# power_supply.net
KiCad netlist of a schematic drawn in Altium Designer
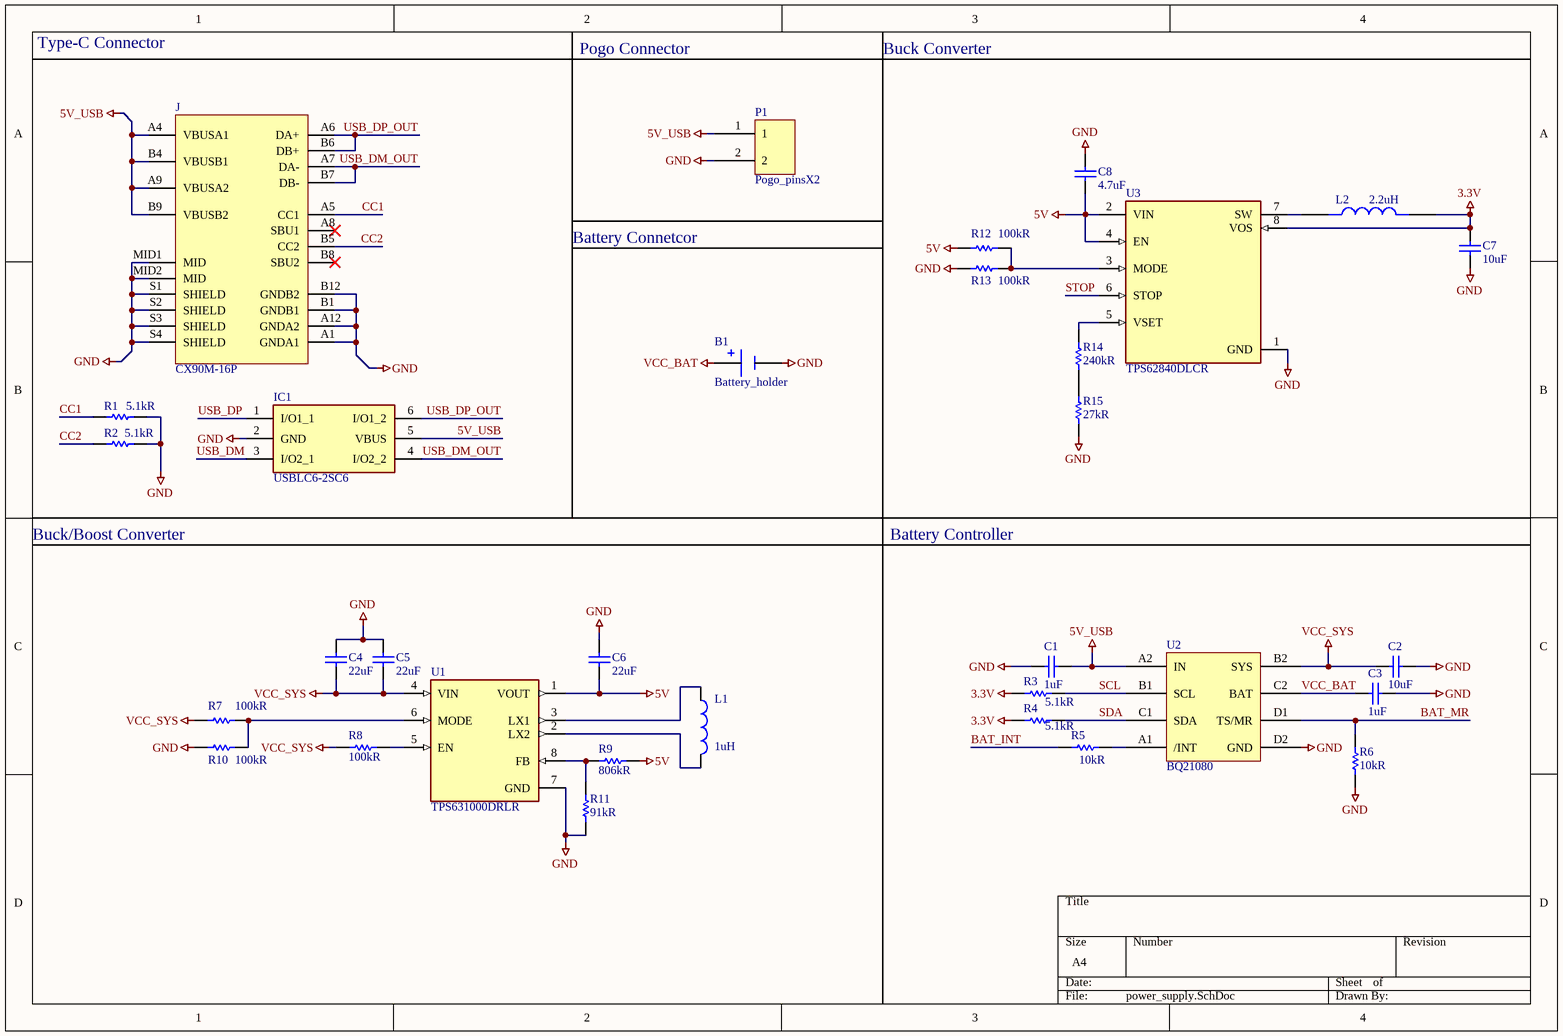
[diagram p0: power_supply.SchDoc]

(export (version "E")
  (design (tool "Eeschema 10.0.6"))
  (components
    (comp (ref "B1")
      (value "Battery_holder")
      (footprint "CHOCO_KEYBOARD:battery connection")
      (description "li-ion 14500 battery holder")
      (libsource (lib "CHOCO_KEYBOARD") (part "Battery_holder"))
    )
    (comp (ref "C1")
      (value "1uF")
      (footprint "CAP_0402")
      (fields (field (name "MF") "Murata") (field (name "MP") "GRM022R60J222KE19L"))
      (libsource (lib "CAP_SMD") (part "Cap_1uF_0402"))
    )
    (comp (ref "C2")
      (value "10uF")
      (footprint "CAP_0402")
      (fields (field (name "MF") "Murata") (field (name "MP") "GRM022R60J222KE19L"))
      (libsource (lib "CAP_SMD") (part "Cap_10uF_0402"))
    )
    (comp (ref "C3")
      (value "1uF")
      (footprint "CAP_0402")
      (fields (field (name "MF") "Murata") (field (name "MP") "GRM022R60J222KE19L"))
      (libsource (lib "CAP_SMD") (part "Cap_1uF_0402"))
    )
    (comp (ref "C4")
      (value "22uF")
      (footprint "CAP_0402")
      (fields (field (name "MF") "Murata") (field (name "MP") "GRM022R60J222KE19L"))
      (libsource (lib "CAP_SMD") (part "Cap_22uF_0402"))
    )
    (comp (ref "C5")
      (value "22uF")
      (footprint "CAP_0402")
      (fields (field (name "MF") "Murata") (field (name "MP") "GRM022R60J222KE19L"))
      (libsource (lib "CAP_SMD") (part "Cap_22uF_0402"))
    )
    (comp (ref "C6")
      (value "22uF")
      (footprint "CAP_0402")
      (fields (field (name "MF") "Murata") (field (name "MP") "GRM022R60J222KE19L"))
      (libsource (lib "CAP_SMD") (part "Cap_22uF_0402"))
    )
    (comp (ref "C7")
      (value "10uF")
      (footprint "CAP_0402")
      (fields (field (name "MF") "Murata") (field (name "MP") "GRM022R60J222KE19L"))
      (libsource (lib "CAP_SMD") (part "Cap_10uF_0402"))
    )
    (comp (ref "C8")
      (value "4.7uF")
      (footprint "CAP_0402")
      (fields (field (name "MF") "Murata") (field (name "MP") "GRM022R60J222KE19L"))
      (libsource (lib "CAP_SMD") (part "Cap_4.7uF_0402"))
    )
    (comp (ref "IC1")
      (value "USBLC6-2SC6")
      (footprint "SOT95P280X145-6N")
      (description "Integrated Circuit")
      (fields (field (name "MOUSER PART NUMBER") "511-USBLC6-2SC6"))
      (libsource (lib "CHOCO_KEYBOARD") (part "USBLC6-2SC6"))
    )
    (comp (ref "J")
      (value "CX90M-16P")
      (footprint "CHOCO_KEYBOARD:HRS_CX90M-16P")
      (fields (field (name "MF") "Hirose Electric Co Ltd"))
      (libsource (lib "CHOCO_KEYBOARD") (part "CX90M-16P"))
    )
    (comp (ref "L1")
      (value "1uH")
      (footprint "INDC1608X100N")
      (description "DFE18SAN1R0MG0L")
      (libsource (lib "DFE18SAN1R0MG0L") (part "DFE18SAN1R0MG0L"))
    )
    (comp (ref "L2")
      (value "2.2uH")
      (footprint "INDC2012X100N")
      (description "2.2 ÂµH Shielded Multilayer Inductor 800 mA 299mOhm Max 0805 (2012 Metric)")
      (fields (field (name "MF") "TDK") (field (name "MP") "MLP2012S2R2MT0S1"))
      (libsource (lib "MLP2012S2R2MT0S1") (part "MLP2012S2R2MT0S1"))
    )
    (comp (ref "P1")
      (value "Pogo_pinsX2")
      (footprint "pogo_2_pins_amgled")
      (libsource (lib "CHOCO_KEYBOARD") (part "Pogo_pinsX2"))
    )
    (comp (ref "R1")
      (value "5.1kR")
      (footprint "RES_0402")
      (libsource (lib "RES_SMD") (part "Res_5.1kR_0402"))
    )
    (comp (ref "R2")
      (value "5.1kR")
      (footprint "RES_0402")
      (libsource (lib "RES_SMD") (part "Res_5.1kR_0402"))
    )
    (comp (ref "R3")
      (value "5.1kR")
      (footprint "RES_0402")
      (libsource (lib "RES_SMD") (part "Res_5.1kR_0402"))
    )
    (comp (ref "R4")
      (value "5.1kR")
      (footprint "RES_0402")
      (libsource (lib "RES_SMD") (part "Res_5.1kR_0402"))
    )
    (comp (ref "R5") (value "10kR") (footprint "RES_0402") (libsource (lib "RES_SMD") (part "Res_10kR_0402")))
    (comp (ref "R6") (value "10kR") (footprint "RES_0402") (libsource (lib "RES_SMD") (part "Res_10kR_0402")))
    (comp (ref "R7")
      (value "100kR")
      (footprint "RES_0402")
      (libsource (lib "RES_SMD") (part "Res_100kR_0402_1"))
    )
    (comp (ref "R8")
      (value "100kR")
      (footprint "RES_0402")
      (libsource (lib "RES_SMD") (part "Res_100kR_0402_1"))
    )
    (comp (ref "R9")
      (value "806kR")
      (footprint "RES_0402")
      (libsource (lib "RES_SMD") (part "Res_806kR_0402_1"))
    )
    (comp (ref "R10")
      (value "100kR")
      (footprint "RES_0402")
      (libsource (lib "RES_SMD") (part "Res_100kR_0402_1"))
    )
    (comp (ref "R11")
      (value "91kR")
      (footprint "RES_0402")
      (libsource (lib "RES_SMD") (part "Res_91kR_0402"))
    )
    (comp (ref "R12")
      (value "100kR")
      (footprint "RES_0402")
      (libsource (lib "RES_SMD") (part "Res_100kR_0402_1"))
    )
    (comp (ref "R13")
      (value "100kR")
      (footprint "RES_0402")
      (libsource (lib "RES_SMD") (part "Res_100kR_0402_1"))
    )
    (comp (ref "R14")
      (value "240kR")
      (footprint "RES_0402")
      (libsource (lib "RES_SMD") (part "Res_240kR_0402"))
    )
    (comp (ref "R15")
      (value "27kR")
      (footprint "RES_0402")
      (libsource (lib "RES_SMD") (part "Res_27kR_0402"))
    )
    (comp (ref "U1")
      (value "TPS631000DRLR")
      (footprint "SOT50P160X60-8N")
      (description "1.5-A output current, high-power-density buck-boost converter")
      (fields (field (name "MF") "Texas Instruments"))
      (libsource (lib "TPS631000DRLR") (part "TPS631000DRLR"))
    )
    (comp (ref "U2")
      (value "BQ21080")
      (footprint "IC_BQ25180YBGR")
      (description "Battery Managment IC")
      (libsource (lib "CHOCO_KEYBOARD") (part "BQ21080"))
    )
    (comp (ref "U3")
      (value "TPS62840DLCR")
      (footprint "SON50P200X150X100-8N")
      (libsource (lib "TPS62840DLCR") (part "TPS62840DLCR"))
    )
  )
  (nets
    (net (code "1") (name "/BAT_INT") (class "Default")
      (node (ref "R5") (pin "2") (pinfunction "2_2") (pintype "passive"))
    )
    (net (code "2") (name "/BAT_MR") (class "Default")
      (node (ref "R6") (pin "1") (pinfunction "1_1") (pintype "passive"))
      (node (ref "U2") (pin "D1") (pinfunction "TS/MR_D1") (pintype "passive"))
    )
    (net (code "3") (name "/CC1") (class "Default")
      (node (ref "J") (pin "A5") (pinfunction "CC1_A5") (pintype "passive"))
      (node (ref "R1") (pin "1") (pinfunction "1_1") (pintype "passive"))
    )
    (net (code "4") (name "/CC2") (class "Default")
      (node (ref "J") (pin "B5") (pinfunction "CC2_B5") (pintype "passive"))
      (node (ref "R2") (pin "1") (pinfunction "1_1") (pintype "passive"))
    )
    (net (code "5") (name "/SCL") (class "Default")
      (node (ref "R3") (pin "1") (pinfunction "1_1") (pintype "passive"))
      (node (ref "U2") (pin "B1") (pinfunction "SCL_B1") (pintype "passive"))
    )
    (net (code "6") (name "/SDA") (class "Default")
      (node (ref "R4") (pin "1") (pinfunction "1_1") (pintype "passive"))
      (node (ref "U2") (pin "C1") (pinfunction "SDA_C1") (pintype "passive"))
    )
    (net (code "7") (name "/STOP") (class "Default")
      (node (ref "U3") (pin "6") (pinfunction "STOP_6") (pintype "input"))
    )
    (net (code "8") (name "/USB_DM") (class "Default")
      (node (ref "IC1") (pin "3") (pinfunction "I/O2_1_3") (pintype "passive"))
    )
    (net (code "9") (name "/USB_DM_OUT") (class "Default")
      (node (ref "IC1") (pin "4") (pinfunction "I/O2_2_4") (pintype "passive"))
      (node (ref "J") (pin "A7") (pinfunction "DA-_A7") (pintype "passive"))
      (node (ref "J") (pin "B7") (pinfunction "DB-_B7") (pintype "passive"))
    )
    (net (code "10") (name "/USB_DP") (class "Default")
      (node (ref "IC1") (pin "1") (pinfunction "I/O1_1_1") (pintype "passive"))
    )
    (net (code "11") (name "/USB_DP_OUT") (class "Default")
      (node (ref "IC1") (pin "6") (pinfunction "I/O1_2_6") (pintype "passive"))
      (node (ref "J") (pin "A6") (pinfunction "DA+_A6") (pintype "passive"))
      (node (ref "J") (pin "B6") (pinfunction "DB+_B6") (pintype "passive"))
    )
    (net (code "12") (name "3.3V") (class "Default")
      (node (ref "C7") (pin "2") (pinfunction "2_2") (pintype "passive"))
      (node (ref "L2") (pin "2") (pinfunction "2_2") (pintype "passive"))
      (node (ref "R3") (pin "2") (pinfunction "2_2") (pintype "passive"))
      (node (ref "R4") (pin "2") (pinfunction "2_2") (pintype "passive"))
      (node (ref "U3") (pin "8") (pinfunction "VOS_8") (pintype "input"))
    )
    (net (code "13") (name "5V") (class "Default")
      (node (ref "C6") (pin "1") (pinfunction "1_1") (pintype "passive"))
      (node (ref "C8") (pin "2") (pinfunction "2_2") (pintype "passive"))
      (node (ref "R12") (pin "1") (pinfunction "1_1") (pintype "passive"))
      (node (ref "R9") (pin "1") (pinfunction "1_1") (pintype "passive"))
      (node (ref "U1") (pin "1") (pinfunction "VOUT_1") (pintype "output"))
      (node (ref "U3") (pin "2") (pinfunction "VIN_2") (pintype "power_in"))
      (node (ref "U3") (pin "4") (pinfunction "EN_4") (pintype "input"))
    )
    (net (code "14") (name "5V_USB") (class "Default")
      (node (ref "C1") (pin "2") (pinfunction "2_2") (pintype "passive"))
      (node (ref "IC1") (pin "5") (pinfunction "VBUS_5") (pintype "passive"))
      (node (ref "J") (pin "A4") (pinfunction "VBUSA1_A4") (pintype "power_in"))
      (node (ref "J") (pin "A9") (pinfunction "VBUSA2_A9") (pintype "power_in"))
      (node (ref "J") (pin "B4") (pinfunction "VBUSB1_B4") (pintype "power_in"))
      (node (ref "J") (pin "B9") (pinfunction "VBUSB2_B9") (pintype "power_in"))
      (node (ref "P1") (pin "1") (pinfunction "1_1") (pintype "passive"))
      (node (ref "U2") (pin "A2") (pinfunction "IN_A2") (pintype "passive"))
    )
    (net (code "15") (name "GND") (class "Default")
      (node (ref "B1") (pin "2") (pinfunction "NEG_2") (pintype "passive"))
      (node (ref "C1") (pin "1") (pinfunction "1_1") (pintype "passive"))
      (node (ref "C2") (pin "1") (pinfunction "1_1") (pintype "passive"))
      (node (ref "C3") (pin "1") (pinfunction "1_1") (pintype "passive"))
      (node (ref "C4") (pin "2") (pinfunction "2_2") (pintype "passive"))
      (node (ref "C5") (pin "2") (pinfunction "2_2") (pintype "passive"))
      (node (ref "C6") (pin "2") (pinfunction "2_2") (pintype "passive"))
      (node (ref "C7") (pin "1") (pinfunction "1_1") (pintype "passive"))
      (node (ref "C8") (pin "1") (pinfunction "1_1") (pintype "passive"))
      (node (ref "IC1") (pin "2") (pinfunction "GND_2") (pintype "passive"))
      (node (ref "J") (pin "A1") (pinfunction "GNDA1_A1") (pintype "power_in"))
      (node (ref "J") (pin "A12") (pinfunction "GNDA2_A12") (pintype "power_in"))
      (node (ref "J") (pin "B1") (pinfunction "GNDB1_B1") (pintype "power_in"))
      (node (ref "J") (pin "B12") (pinfunction "GNDB2_B12") (pintype "power_in"))
      (node (ref "J") (pin "MID1") (pinfunction "MID_MID1") (pintype "passive"))
      (node (ref "J") (pin "MID2") (pinfunction "MID_MID2") (pintype "passive"))
      (node (ref "J") (pin "S1") (pinfunction "SHIELD_S1") (pintype "passive"))
      (node (ref "J") (pin "S2") (pinfunction "SHIELD_S2") (pintype "passive"))
      (node (ref "J") (pin "S3") (pinfunction "SHIELD_S3") (pintype "passive"))
      (node (ref "J") (pin "S4") (pinfunction "SHIELD_S4") (pintype "passive"))
      (node (ref "P1") (pin "2") (pinfunction "2_2") (pintype "passive"))
      (node (ref "R1") (pin "2") (pinfunction "2_2") (pintype "passive"))
      (node (ref "R10") (pin "1") (pinfunction "1_1") (pintype "passive"))
      (node (ref "R11") (pin "1") (pinfunction "1_1") (pintype "passive"))
      (node (ref "R13") (pin "1") (pinfunction "1_1") (pintype "passive"))
      (node (ref "R15") (pin "1") (pinfunction "1_1") (pintype "passive"))
      (node (ref "R2") (pin "2") (pinfunction "2_2") (pintype "passive"))
      (node (ref "R6") (pin "2") (pinfunction "2_2") (pintype "passive"))
      (node (ref "U1") (pin "7") (pinfunction "GND_7") (pintype "power_in"))
      (node (ref "U2") (pin "D2") (pinfunction "GND_D2") (pintype "passive"))
      (node (ref "U3") (pin "1") (pinfunction "GND_1") (pintype "power_in"))
    )
    (net (code "16") (name "Net-(R14-Pad2)") (class "Default")
      (node (ref "R14") (pin "2") (pinfunction "2_2") (pintype "passive"))
      (node (ref "R15") (pin "2") (pinfunction "2_2") (pintype "passive"))
    )
    (net (code "17") (name "Net-(U1-EN)") (class "Default")
      (node (ref "R8") (pin "2") (pinfunction "2_2") (pintype "passive"))
      (node (ref "U1") (pin "5") (pinfunction "EN_5") (pintype "input"))
    )
    (net (code "18") (name "Net-(U1-FB)") (class "Default")
      (node (ref "R11") (pin "2") (pinfunction "2_2") (pintype "passive"))
      (node (ref "R9") (pin "2") (pinfunction "2_2") (pintype "passive"))
      (node (ref "U1") (pin "8") (pinfunction "FB_8") (pintype "input"))
    )
    (net (code "19") (name "Net-(U1-LX1)") (class "Default")
      (node (ref "L1") (pin "1") (pinfunction "1_1") (pintype "passive"))
      (node (ref "U1") (pin "3") (pinfunction "LX1_3") (pintype "output"))
    )
    (net (code "20") (name "Net-(U1-LX2)") (class "Default")
      (node (ref "L1") (pin "2") (pinfunction "2_2") (pintype "passive"))
      (node (ref "U1") (pin "2") (pinfunction "LX2_2") (pintype "output"))
    )
    (net (code "21") (name "Net-(U1-MODE)") (class "Default")
      (node (ref "R10") (pin "2") (pinfunction "2_2") (pintype "passive"))
      (node (ref "R7") (pin "2") (pinfunction "2_2") (pintype "passive"))
      (node (ref "U1") (pin "6") (pinfunction "MODE_6") (pintype "input"))
    )
    (net (code "22") (name "Net-(U2-{slash}INT)") (class "Default")
      (node (ref "R5") (pin "1") (pinfunction "1_1") (pintype "passive"))
      (node (ref "U2") (pin "A1") (pinfunction "/INT_A1") (pintype "passive"))
    )
    (net (code "23") (name "Net-(U3-MODE)") (class "Default")
      (node (ref "R12") (pin "2") (pinfunction "2_2") (pintype "passive"))
      (node (ref "R13") (pin "2") (pinfunction "2_2") (pintype "passive"))
      (node (ref "U3") (pin "3") (pinfunction "MODE_3") (pintype "input"))
    )
    (net (code "24") (name "Net-(U3-SW)") (class "Default")
      (node (ref "L2") (pin "1") (pinfunction "1_1") (pintype "passive"))
      (node (ref "U3") (pin "7") (pinfunction "SW_7") (pintype "power_in"))
    )
    (net (code "25") (name "Net-(U3-VSET)") (class "Default")
      (node (ref "R14") (pin "1") (pinfunction "1_1") (pintype "passive"))
      (node (ref "U3") (pin "5") (pinfunction "VSET_5") (pintype "input"))
    )
    (net (code "26") (name "VCC_BAT") (class "Default")
      (node (ref "B1") (pin "1") (pinfunction "POS_1") (pintype "passive"))
      (node (ref "C3") (pin "2") (pinfunction "2_2") (pintype "passive"))
      (node (ref "U2") (pin "C2") (pinfunction "BAT_C2") (pintype "passive"))
    )
    (net (code "27") (name "VCC_SYS") (class "Default")
      (node (ref "C2") (pin "2") (pinfunction "2_2") (pintype "passive"))
      (node (ref "C4") (pin "1") (pinfunction "1_1") (pintype "passive"))
      (node (ref "C5") (pin "1") (pinfunction "1_1") (pintype "passive"))
      (node (ref "R7") (pin "1") (pinfunction "1_1") (pintype "passive"))
      (node (ref "R8") (pin "1") (pinfunction "1_1") (pintype "passive"))
      (node (ref "U1") (pin "4") (pinfunction "VIN_4") (pintype "input"))
      (node (ref "U2") (pin "B2") (pinfunction "SYS_B2") (pintype "passive"))
    )
    (net (code "28") (name "unconnected-(J-SBU1-PadA8)") (class "Default")
      (node (ref "J") (pin "A8") (pinfunction "SBU1_A8") (pintype "passive+no_connect"))
    )
    (net (code "29") (name "unconnected-(J-SBU2-PadB8)") (class "Default")
      (node (ref "J") (pin "B8") (pinfunction "SBU2_B8") (pintype "passive+no_connect"))
    )
  )
)
